# source_A.net
KiCad netlist of a schematic drawn in Altium Designer
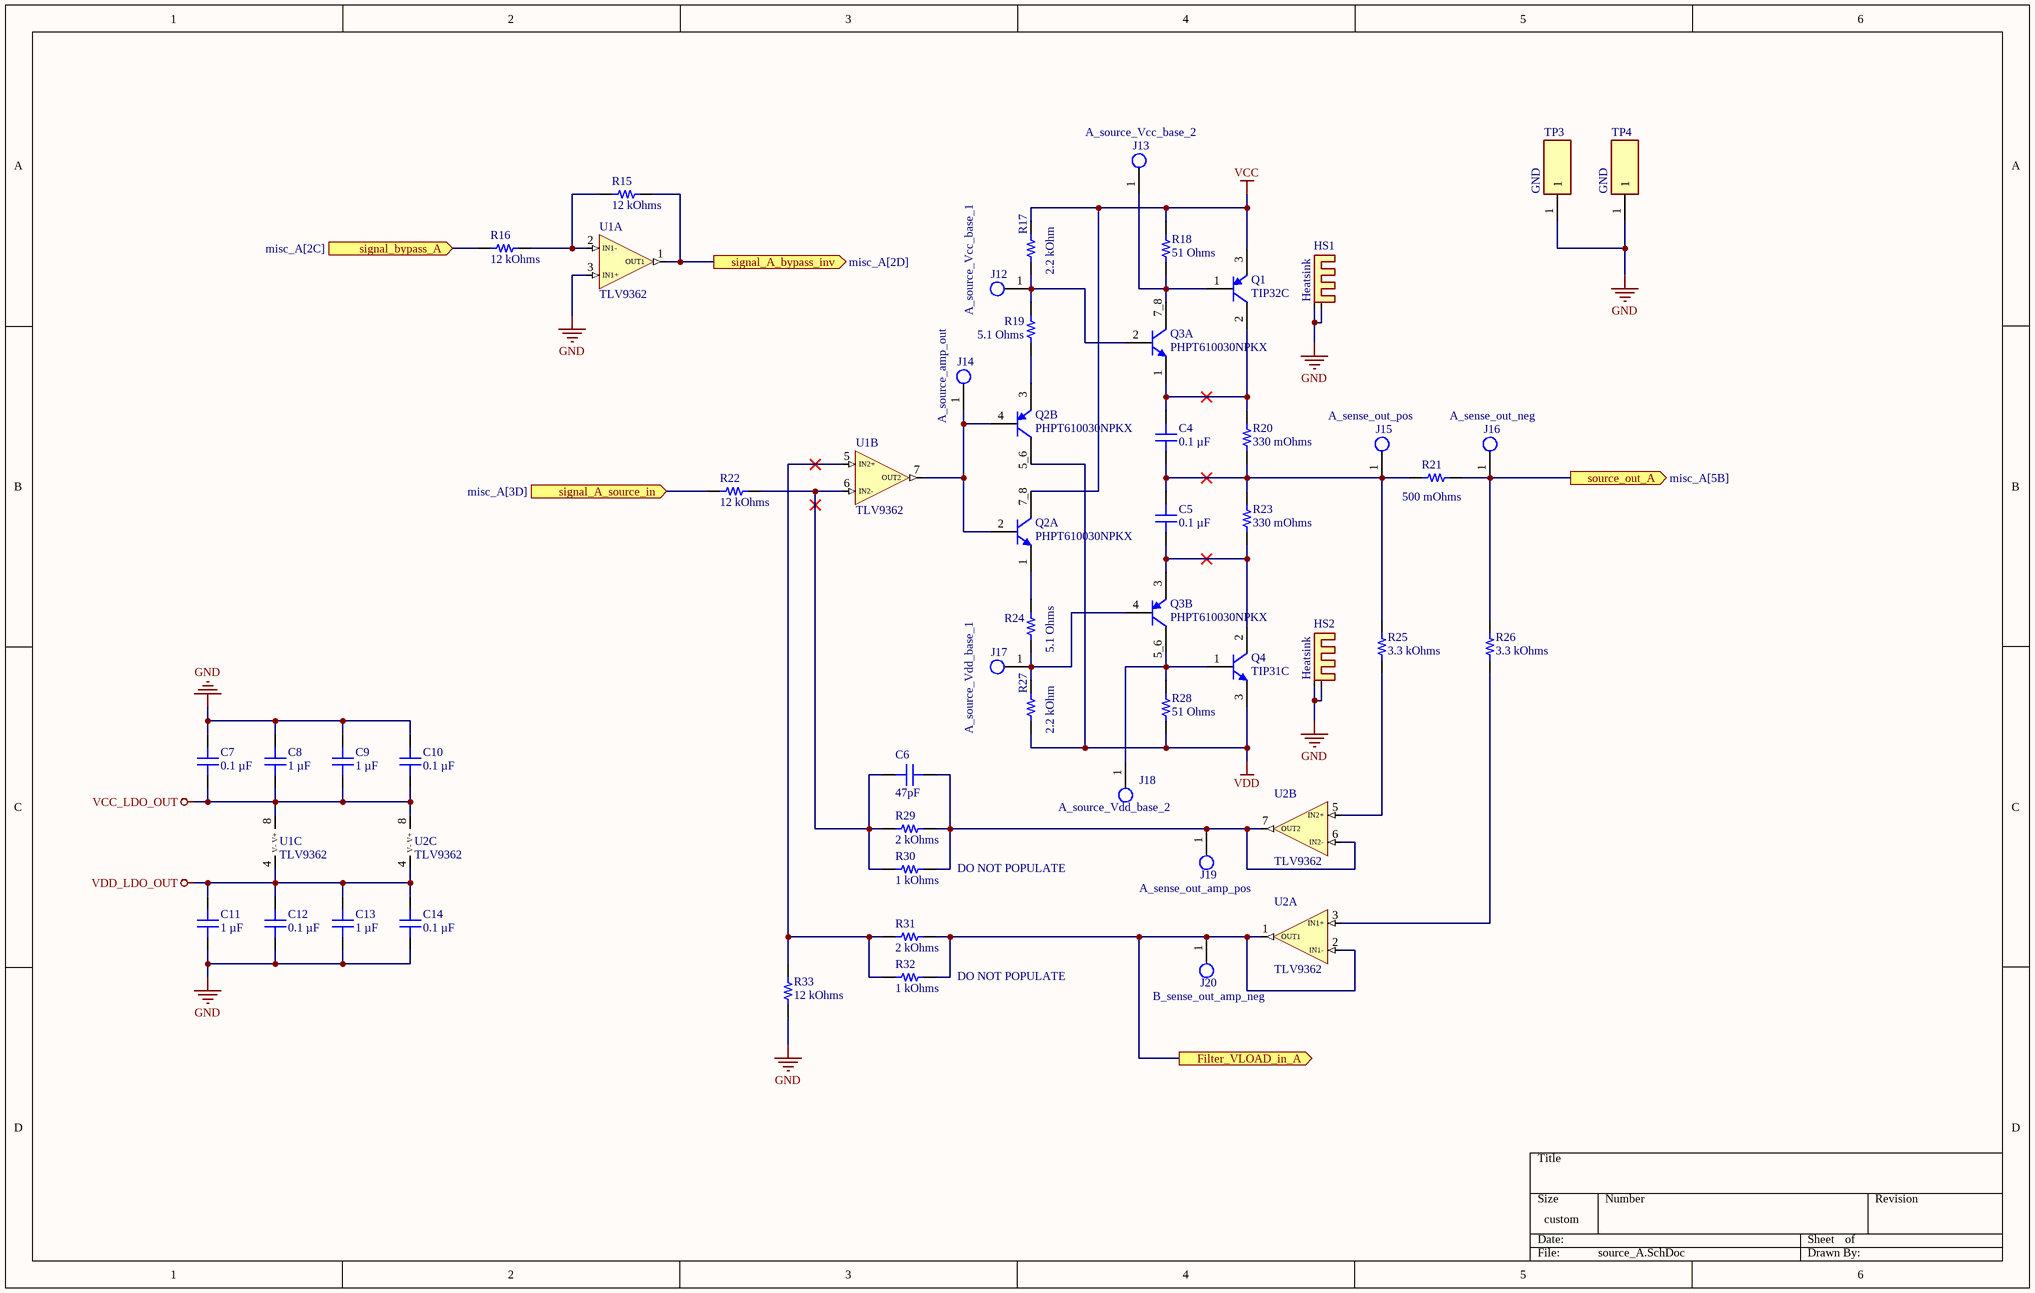
[diagram p0: source_A.SchDoc]

(export (version "E")
  (design (tool "Eeschema 10.0.6"))
  (components
    (comp (ref "C4")
      (value "0.1 µF")
      (footprint "CAP 1206_3216 - 0.8MM")
      (description "CAP CER 0.1UF 50V X7R 1206")
      (fields
        (field (name "PART NUMBER") "885012208087")
        (field (name "CAPACITANCE") "0.1 µF")
        (field (name "MANUFACTURER") "Würth Elektronik")
      )
      (libsource (lib "Celestial Altium Library - altium_library") (part "Capacitor"))
    )
    (comp (ref "C5")
      (value "0.1 µF")
      (footprint "CAP 1206_3216 - 0.8MM")
      (description "CAP CER 0.1UF 50V X7R 1206")
      (fields
        (field (name "PART NUMBER") "885012208087")
        (field (name "CAPACITANCE") "0.1 µF")
        (field (name "MANUFACTURER") "Würth Elektronik")
      )
      (libsource (lib "Celestial Altium Library - altium_library") (part "Capacitor"))
    )
    (comp (ref "C6")
      (value "47pF")
      (footprint "CAP 1206_3216 - 1.8MM")
      (description "CAP CER 47PF 1KV C0G/NP0 1206")
      (fields
        (field (name "PART NUMBER") "1206AA470KAT1A")
        (field (name "CAPACITANCE") "47pF")
        (field (name "MANUFACTURER") "AVX Corporation")
      )
      (libsource (lib "Celestial Altium Library - altium_library") (part "Capacitor"))
    )
    (comp (ref "C7")
      (value "0.1 µF")
      (footprint "CAP 1206_3216 - 0.8MM")
      (description "CAP CER 0.1UF 50V X7R 1206")
      (fields
        (field (name "PART NUMBER") "885012208087")
        (field (name "CAPACITANCE") "0.1 µF")
        (field (name "MANUFACTURER") "Würth Elektronik")
      )
      (libsource (lib "Celestial Altium Library - altium_library") (part "Capacitor"))
    )
    (comp (ref "C8")
      (value "1 µF")
      (footprint "CAP 1206_3216 - 0.8MM")
      (description "CAP CER 1UF 50V X7R 1206")
      (fields
        (field (name "PART NUMBER") "885012208093")
        (field (name "CAPACITANCE") "1 µF")
        (field (name "MANUFACTURER") "Würth Elektronik")
      )
      (libsource (lib "Celestial Altium Library - altium_library") (part "Capacitor"))
    )
    (comp (ref "C9")
      (value "1 µF")
      (footprint "CAP 1206_3216 - 0.8MM")
      (description "CAP CER 1UF 50V X7R 1206")
      (fields
        (field (name "PART NUMBER") "885012208093")
        (field (name "CAPACITANCE") "1 µF")
        (field (name "MANUFACTURER") "Würth Elektronik")
      )
      (libsource (lib "Celestial Altium Library - altium_library") (part "Capacitor"))
    )
    (comp (ref "C10")
      (value "0.1 µF")
      (footprint "CAP 1206_3216 - 0.8MM")
      (description "CAP CER 0.1UF 50V X7R 1206")
      (fields
        (field (name "PART NUMBER") "885012208087")
        (field (name "CAPACITANCE") "0.1 µF")
        (field (name "MANUFACTURER") "Würth Elektronik")
      )
      (libsource (lib "Celestial Altium Library - altium_library") (part "Capacitor"))
    )
    (comp (ref "C11")
      (value "1 µF")
      (footprint "CAP 1206_3216 - 0.8MM")
      (description "CAP CER 1UF 50V X7R 1206")
      (fields
        (field (name "PART NUMBER") "885012208093")
        (field (name "CAPACITANCE") "1 µF")
        (field (name "MANUFACTURER") "Würth Elektronik")
      )
      (libsource (lib "Celestial Altium Library - altium_library") (part "Capacitor"))
    )
    (comp (ref "C12")
      (value "0.1 µF")
      (footprint "CAP 1206_3216 - 0.8MM")
      (description "CAP CER 0.1UF 50V X7R 1206")
      (fields
        (field (name "PART NUMBER") "885012208087")
        (field (name "CAPACITANCE") "0.1 µF")
        (field (name "MANUFACTURER") "Würth Elektronik")
      )
      (libsource (lib "Celestial Altium Library - altium_library") (part "Capacitor"))
    )
    (comp (ref "C13")
      (value "1 µF")
      (footprint "CAP 1206_3216 - 0.8MM")
      (description "CAP CER 1UF 50V X7R 1206")
      (fields
        (field (name "PART NUMBER") "885012208093")
        (field (name "CAPACITANCE") "1 µF")
        (field (name "MANUFACTURER") "Würth Elektronik")
      )
      (libsource (lib "Celestial Altium Library - altium_library") (part "Capacitor"))
    )
    (comp (ref "C14")
      (value "0.1 µF")
      (footprint "CAP 1206_3216 - 0.8MM")
      (description "CAP CER 0.1UF 50V X7R 1206")
      (fields
        (field (name "PART NUMBER") "885012208087")
        (field (name "CAPACITANCE") "0.1 µF")
        (field (name "MANUFACTURER") "Würth Elektronik")
      )
      (libsource (lib "Celestial Altium Library - altium_library") (part "Capacitor"))
    )
    (comp (ref "HS1")
      (value "Heatsink")
      (footprint "593002B03400G")
      (description "593002B03400G Heatsink TO220 13.4 C/W")
      (fields
        (field (name "MANUFACTURER_PART_NUMBER") "593002B03400G")
        (field (name "MOUSER PART NUMBER") "532-593002B03400G")
      )
      (libsource (lib "za_koncar") (part "593002B03400G"))
    )
    (comp (ref "HS2")
      (value "Heatsink")
      (footprint "593002B03400G")
      (description "593002B03400G Heatsink TO220 13.4 C/W")
      (fields
        (field (name "MANUFACTURER_PART_NUMBER") "593002B03400G")
        (field (name "MOUSER PART NUMBER") "532-593002B03400G")
      )
      (libsource (lib "za_koncar") (part "593002B03400G"))
    )
    (comp (ref "J12")
      (value "A_source_Vcc_base_1")
      (footprint "FP-5001-MFG")
      (description "PC TEST POINT MINIATURE BLACK")
      (libsource (lib "za_koncar") (part "5001"))
    )
    (comp (ref "J13")
      (value "A_source_Vcc_base_2")
      (footprint "FP-5001-MFG")
      (description "PC TEST POINT MINIATURE BLACK")
      (libsource (lib "za_koncar") (part "5001"))
    )
    (comp (ref "J14")
      (value "A_source_amp_out")
      (footprint "FP-5001-MFG")
      (description "PC TEST POINT MINIATURE BLACK")
      (libsource (lib "za_koncar") (part "5001"))
    )
    (comp (ref "J15")
      (value "A_sense_out_pos")
      (footprint "FP-5001-MFG")
      (description "PC TEST POINT MINIATURE BLACK")
      (libsource (lib "za_koncar") (part "5001"))
    )
    (comp (ref "J16")
      (value "A_sense_out_neg")
      (footprint "FP-5001-MFG")
      (description "PC TEST POINT MINIATURE BLACK")
      (libsource (lib "za_koncar") (part "5001"))
    )
    (comp (ref "J17")
      (value "A_source_Vdd_base_1")
      (footprint "FP-5001-MFG")
      (description "PC TEST POINT MINIATURE BLACK")
      (libsource (lib "za_koncar") (part "5001"))
    )
    (comp (ref "J18")
      (value "A_source_Vdd_base_2")
      (footprint "FP-5001-MFG")
      (description "PC TEST POINT MINIATURE BLACK")
      (libsource (lib "za_koncar") (part "5001"))
    )
    (comp (ref "J19")
      (value "A_sense_out_amp_pos")
      (footprint "FP-5001-MFG")
      (description "PC TEST POINT MINIATURE BLACK")
      (libsource (lib "za_koncar") (part "5001"))
    )
    (comp (ref "J20")
      (value "B_sense_out_amp_neg")
      (footprint "FP-5001-MFG")
      (description "PC TEST POINT MINIATURE BLACK")
      (libsource (lib "za_koncar") (part "5001"))
    )
    (comp (ref "Q1")
      (value "TIP32C")
      (footprint "ONSC-TO-220-3-221A-09")
      (description "Complementary Silicon Plastic Power Transistor, 3-Pin TO-220, Tube")
      (fields (field (name "MANUFACTURER") "On Semiconductor"))
      (libsource (lib "ON Semi General Purpose Transistors") (part "TIP32C"))
    )
    (comp (ref "Q2")
      (value "PHPT610030NPKX")
      (footprint "TRANS_BUK9K18-40E,115")
      (libsource (lib "za_koncar") (part "PHPT610030NPK"))
    )
    (comp (ref "Q3")
      (value "PHPT610030NPKX")
      (footprint "TRANS_BUK9K18-40E,115")
      (libsource (lib "za_koncar") (part "PHPT610030NPK"))
    )
    (comp (ref "Q4")
      (value "TIP31C")
      (footprint "ONSC-TO-220-3-221A-09")
      (description "Complementary Silicon Plastic Power Transistor, 3-Pin TO-220, Tube")
      (fields (field (name "MANUFACTURER") "On Semiconductor"))
      (libsource (lib "ON Semi General Purpose Transistors") (part "TIP31C"))
    )
    (comp (ref "R15")
      (value "12 kOhms")
      (footprint "RES 1206_3216")
      (description "RES SMD 12K OHM 0.1% 1/4W 1206")
      (fields
        (field (name "PART NUMBER") "ERA-8AEB123V")
        (field (name "MANUFACTURER") "Panasonic Electronic Components")
      )
      (libsource (lib "Celestial Altium Library - altium_library") (part "Resistor"))
    )
    (comp (ref "R16")
      (value "12 kOhms")
      (footprint "RES 1206_3216")
      (description "RES SMD 12K OHM 0.1% 1/4W 1206")
      (fields
        (field (name "PART NUMBER") "ERA-8AEB123V")
        (field (name "MANUFACTURER") "Panasonic Electronic Components")
      )
      (libsource (lib "Celestial Altium Library - altium_library") (part "Resistor"))
    )
    (comp (ref "R17")
      (value "2.2 kOhm")
      (footprint "za_koncar:RESC3116X65N")
      (description "Resistor")
      (fields
        (field (name "MANUFACTURER_PART_NUMBER") "RT1206FRE072K2L")
        (field (name "MOUSER PART NUMBER") "603-RT1206FRE072K2L")
      )
      (libsource (lib "za_koncar") (part "RT1206FRE072K2L"))
    )
    (comp (ref "R18")
      (value "51 Ohms")
      (footprint "RES 1206_3216")
      (description "RES SMD 51 OHM 5% 1/4W 1206")
      (fields
        (field (name "PART NUMBER") "ERJ-8GEYJ510V")
        (field (name "MANUFACTURER") "Panasonic Electronic Components")
      )
      (libsource (lib "Celestial Altium Library - altium_library") (part "Resistor"))
    )
    (comp (ref "R19")
      (value "5.1 Ohms")
      (footprint "RES 1206_3216")
      (description "RES SMD 5.1 OHM 5% 1/4W 1206")
      (fields
        (field (name "PART NUMBER") "ERJ-8GEYJ5R1V")
        (field (name "MANUFACTURER") "Panasonic Electronic Components")
      )
      (libsource (lib "Celestial Altium Library - altium_library") (part "Resistor"))
    )
    (comp (ref "R20")
      (value "330 mOhms")
      (footprint "STACKPOLE CSR2512")
      (description "RES 0.33 OHM 1% 2W 2512")
      (fields
        (field (name "PART NUMBER") "CSRN2512FKR330")
        (field (name "MANUFACTURER") "Stackpole Electronics Inc")
      )
      (libsource (lib "Celestial Altium Library - altium_library") (part "Resistor"))
    )
    (comp (ref "R21")
      (value "500 mOhms")
      (footprint "STACKPOLE CSR2512")
      (description "RES 0.5 OHM 1% 2W 2512")
      (fields
        (field (name "PART NUMBER") "CSRN2512FKR500")
        (field (name "MANUFACTURER") "Stackpole Electronics Inc")
      )
      (libsource (lib "Celestial Altium Library - altium_library") (part "Resistor"))
    )
    (comp (ref "R22")
      (value "12 kOhms")
      (footprint "RES 1206_3216")
      (description "RES SMD 12K OHM 0.1% 1/4W 1206")
      (fields
        (field (name "PART NUMBER") "ERA-8AEB123V")
        (field (name "MANUFACTURER") "Panasonic Electronic Components")
      )
      (libsource (lib "Celestial Altium Library - altium_library") (part "Resistor"))
    )
    (comp (ref "R23")
      (value "330 mOhms")
      (footprint "STACKPOLE CSR2512")
      (description "RES 0.33 OHM 1% 2W 2512")
      (fields
        (field (name "PART NUMBER") "CSRN2512FKR330")
        (field (name "MANUFACTURER") "Stackpole Electronics Inc")
      )
      (libsource (lib "Celestial Altium Library - altium_library") (part "Resistor"))
    )
    (comp (ref "R24")
      (value "5.1 Ohms")
      (footprint "RES 1206_3216")
      (description "RES SMD 5.1 OHM 5% 1/4W 1206")
      (fields
        (field (name "PART NUMBER") "ERJ-8GEYJ5R1V")
        (field (name "MANUFACTURER") "Panasonic Electronic Components")
      )
      (libsource (lib "Celestial Altium Library - altium_library") (part "Resistor"))
    )
    (comp (ref "R25")
      (value "3.3 kOhms")
      (footprint "YAGEO RES 1206_3216")
      (description "RES SMD 3.3K OHM 1% 1/4W 1206")
      (fields (field (name "PART NUMBER") "RT1206FRE073K3L") (field (name "MANUFACTURER") "Yageo"))
      (libsource (lib "Celestial Altium Library - altium_library") (part "Resistor"))
    )
    (comp (ref "R26")
      (value "3.3 kOhms")
      (footprint "YAGEO RES 1206_3216")
      (description "RES SMD 3.3K OHM 1% 1/4W 1206")
      (fields (field (name "PART NUMBER") "RT1206FRE073K3L") (field (name "MANUFACTURER") "Yageo"))
      (libsource (lib "Celestial Altium Library - altium_library") (part "Resistor"))
    )
    (comp (ref "R27")
      (value "2.2 kOhm")
      (footprint "za_koncar:RESC3116X65N")
      (description "Resistor")
      (fields
        (field (name "MANUFACTURER_PART_NUMBER") "RT1206FRE072K2L")
        (field (name "MOUSER PART NUMBER") "603-RT1206FRE072K2L")
      )
      (libsource (lib "za_koncar") (part "RT1206FRE072K2L"))
    )
    (comp (ref "R28")
      (value "51 Ohms")
      (footprint "RES 1206_3216")
      (description "RES SMD 51 OHM 5% 1/4W 1206")
      (fields
        (field (name "PART NUMBER") "ERJ-8GEYJ510V")
        (field (name "MANUFACTURER") "Panasonic Electronic Components")
      )
      (libsource (lib "Celestial Altium Library - altium_library") (part "Resistor"))
    )
    (comp (ref "R29")
      (value "2 kOhms")
      (footprint "RES 1206_3216")
      (description "RES SMD 2K OHM 0.1% 1/4W 1206")
      (fields
        (field (name "PART NUMBER") "ERA-8AEB202V")
        (field (name "MANUFACTURER") "Panasonic Electronic Components")
      )
      (libsource (lib "Celestial Altium Library - altium_library") (part "Resistor"))
    )
    (comp (ref "R30")
      (value "1 kOhms")
      (footprint "RES 1206_3216")
      (description "RES SMD 1K OHM 0.1% 1/4W 1206")
      (fields
        (field (name "PART NUMBER") "ERA-8AEB102V")
        (field (name "MANUFACTURER") "Panasonic Electronic Components")
      )
      (libsource (lib "Celestial Altium Library - altium_library") (part "Resistor"))
    )
    (comp (ref "R31")
      (value "2 kOhms")
      (footprint "RES 1206_3216")
      (description "RES SMD 2K OHM 0.1% 1/4W 1206")
      (fields
        (field (name "PART NUMBER") "ERA-8AEB202V")
        (field (name "MANUFACTURER") "Panasonic Electronic Components")
      )
      (libsource (lib "Celestial Altium Library - altium_library") (part "Resistor"))
    )
    (comp (ref "R32")
      (value "1 kOhms")
      (footprint "RES 1206_3216")
      (description "RES SMD 1K OHM 0.1% 1/4W 1206")
      (fields
        (field (name "PART NUMBER") "ERA-8AEB102V")
        (field (name "MANUFACTURER") "Panasonic Electronic Components")
      )
      (libsource (lib "Celestial Altium Library - altium_library") (part "Resistor"))
    )
    (comp (ref "R33")
      (value "12 kOhms")
      (footprint "RES 1206_3216")
      (description "RES SMD 12K OHM 0.1% 1/4W 1206")
      (fields
        (field (name "PART NUMBER") "ERA-8AEB123V")
        (field (name "MANUFACTURER") "Panasonic Electronic Components")
      )
      (libsource (lib "Celestial Altium Library - altium_library") (part "Resistor"))
    )
    (comp (ref "TP3")
      (value "GND")
      (footprint "za_koncar:S175146R")
      (description "Test Point")
      (fields
        (field (name "MANUFACTURER_PART_NUMBER") "S1751-46R")
        (field (name "MOUSER PART NUMBER") "855-S1751-46R")
      )
      (libsource (lib "za_koncar") (part "S1751-46R"))
    )
    (comp (ref "TP4")
      (value "GND")
      (footprint "za_koncar:S175146R")
      (description "Test Point")
      (fields
        (field (name "MANUFACTURER_PART_NUMBER") "S1751-46R")
        (field (name "MOUSER PART NUMBER") "855-S1751-46R")
      )
      (libsource (lib "za_koncar") (part "S1751-46R"))
    )
    (comp (ref "U1")
      (value "TLV9362")
      (footprint "SOIC8-127P600X175-8N")
      (description "TLV936x 10-MHz, 40-V, RRO, Operational Amplifie")
      (libsource (lib "za_koncar") (part "TLV9362"))
    )
    (comp (ref "U2")
      (value "TLV9362")
      (footprint "SOIC8-127P600X175-8N")
      (description "TLV936x 10-MHz, 40-V, RRO, Operational Amplifie")
      (libsource (lib "za_koncar") (part "TLV9362"))
    )
  )
  (nets
    (net (code "1") (name "/Filter_VLOAD_in_A") (class "Default")
      (node (ref "J20") (pin "1") (pinfunction "1_1") (pintype "passive"))
      (node (ref "R31") (pin "2") (pinfunction "2_2") (pintype "passive"))
      (node (ref "R32") (pin "2") (pinfunction "2_2") (pintype "passive"))
      (node (ref "U2") (pin "1") (pinfunction "OUT1_1") (pintype "output"))
      (node (ref "U2") (pin "2") (pinfunction "IN1-_2") (pintype "input"))
    )
    (net (code "2") (name "/signal_A_bypass_inv") (class "Default")
      (node (ref "R15") (pin "2") (pinfunction "2_2") (pintype "passive"))
      (node (ref "U1") (pin "1") (pinfunction "OUT1_1") (pintype "output"))
    )
    (net (code "3") (name "/signal_A_source_in") (class "Default")
      (node (ref "R22") (pin "2") (pinfunction "2_2") (pintype "passive"))
    )
    (net (code "4") (name "/signal_bypass_A") (class "Default")
      (node (ref "R16") (pin "2") (pinfunction "2_2") (pintype "passive"))
    )
    (net (code "5") (name "/source_out_A") (class "Default")
      (node (ref "J16") (pin "1") (pinfunction "1_1") (pintype "passive"))
      (node (ref "R21") (pin "1") (pinfunction "1_1") (pintype "passive"))
      (node (ref "R26") (pin "1") (pinfunction "1_1") (pintype "passive"))
    )
    (net (code "6") (name "GND") (class "Default")
      (node (ref "C10") (pin "2") (pinfunction "2_2") (pintype "passive"))
      (node (ref "C11") (pin "2") (pinfunction "2_2") (pintype "passive"))
      (node (ref "C12") (pin "2") (pinfunction "2_2") (pintype "passive"))
      (node (ref "C13") (pin "2") (pinfunction "2_2") (pintype "passive"))
      (node (ref "C14") (pin "2") (pinfunction "2_2") (pintype "passive"))
      (node (ref "C7") (pin "1") (pinfunction "1_1") (pintype "passive"))
      (node (ref "C8") (pin "1") (pinfunction "1_1") (pintype "passive"))
      (node (ref "C9") (pin "2") (pinfunction "2_2") (pintype "passive"))
      (node (ref "HS1") (pin "1") (pinfunction "1_1") (pintype "passive"))
      (node (ref "HS1") (pin "2") (pinfunction "2_2") (pintype "passive"))
      (node (ref "HS2") (pin "1") (pinfunction "1_1") (pintype "passive"))
      (node (ref "HS2") (pin "2") (pinfunction "2_2") (pintype "passive"))
      (node (ref "R33") (pin "1") (pinfunction "1_1") (pintype "passive"))
      (node (ref "TP3") (pin "1") (pinfunction "1_1") (pintype "passive"))
      (node (ref "TP4") (pin "1") (pinfunction "1_1") (pintype "passive"))
      (node (ref "U1") (pin "3") (pinfunction "IN1+_3") (pintype "input"))
    )
    (net (code "7") (name "Net-(C4-Pad1)") (class "Default")
      (node (ref "C4") (pin "1") (pinfunction "1_1") (pintype "passive"))
      (node (ref "C5") (pin "2") (pinfunction "2_2") (pintype "passive"))
      (node (ref "J15") (pin "1") (pinfunction "1_1") (pintype "passive"))
      (node (ref "R20") (pin "1") (pinfunction "1_1") (pintype "passive"))
      (node (ref "R21") (pin "2") (pinfunction "2_2") (pintype "passive"))
      (node (ref "R23") (pin "2") (pinfunction "2_2") (pintype "passive"))
      (node (ref "R25") (pin "1") (pinfunction "1_1") (pintype "passive"))
    )
    (net (code "8") (name "Net-(Q1-B)") (class "Default")
      (node (ref "J13") (pin "1") (pinfunction "1_1") (pintype "passive"))
      (node (ref "Q1") (pin "1") (pinfunction "B_1") (pintype "passive"))
      (node (ref "Q3") (pin "7_8") (pinfunction "C1_7_8") (pintype "passive"))
      (node (ref "R18") (pin "1") (pinfunction "1_1") (pintype "passive"))
    )
    (net (code "9") (name "Net-(Q1-C)") (class "Default")
      (node (ref "C4") (pin "2") (pinfunction "2_2") (pintype "passive"))
      (node (ref "Q1") (pin "2") (pinfunction "C_2") (pintype "passive"))
      (node (ref "Q3") (pin "1") (pinfunction "E1_1") (pintype "passive"))
      (node (ref "R20") (pin "2") (pinfunction "2_2") (pintype "passive"))
    )
    (net (code "10") (name "Net-(Q2A-B1)") (class "Default")
      (node (ref "J14") (pin "1") (pinfunction "1_1") (pintype "passive"))
      (node (ref "Q2") (pin "2") (pinfunction "B1_2") (pintype "passive"))
      (node (ref "Q2") (pin "4") (pinfunction "B2_4") (pintype "passive"))
      (node (ref "U1") (pin "7") (pinfunction "OUT2_7") (pintype "output"))
    )
    (net (code "11") (name "Net-(Q2A-E1)") (class "Default")
      (node (ref "Q2") (pin "1") (pinfunction "E1_1") (pintype "passive"))
      (node (ref "R24") (pin "2") (pinfunction "2_2") (pintype "passive"))
    )
    (net (code "12") (name "Net-(Q2B-E2)") (class "Default")
      (node (ref "Q2") (pin "3") (pinfunction "E2_3") (pintype "passive"))
      (node (ref "R19") (pin "1") (pinfunction "1_1") (pintype "passive"))
    )
    (net (code "13") (name "Net-(Q3A-B1)") (class "Default")
      (node (ref "J12") (pin "1") (pinfunction "1_1") (pintype "passive"))
      (node (ref "Q3") (pin "2") (pinfunction "B1_2") (pintype "passive"))
      (node (ref "R17") (pin "1") (pinfunction "1_1") (pintype "passive"))
      (node (ref "R19") (pin "2") (pinfunction "2_2") (pintype "passive"))
    )
    (net (code "14") (name "Net-(Q3B-B2)") (class "Default")
      (node (ref "J17") (pin "1") (pinfunction "1_1") (pintype "passive"))
      (node (ref "Q3") (pin "4") (pinfunction "B2_4") (pintype "passive"))
      (node (ref "R24") (pin "1") (pinfunction "1_1") (pintype "passive"))
      (node (ref "R27") (pin "2") (pinfunction "2_2") (pintype "passive"))
    )
    (net (code "15") (name "Net-(Q3B-C2)") (class "Default")
      (node (ref "J18") (pin "1") (pinfunction "1_1") (pintype "passive"))
      (node (ref "Q3") (pin "5_6") (pinfunction "C2_5_6") (pintype "passive"))
      (node (ref "Q4") (pin "1") (pinfunction "B_1") (pintype "passive"))
      (node (ref "R28") (pin "2") (pinfunction "2_2") (pintype "passive"))
    )
    (net (code "16") (name "Net-(Q3B-E2)") (class "Default")
      (node (ref "C5") (pin "1") (pinfunction "1_1") (pintype "passive"))
      (node (ref "Q3") (pin "3") (pinfunction "E2_3") (pintype "passive"))
      (node (ref "Q4") (pin "2") (pinfunction "C_2") (pintype "passive"))
      (node (ref "R23") (pin "1") (pinfunction "1_1") (pintype "passive"))
    )
    (net (code "17") (name "Net-(U1A-IN1-)") (class "Default")
      (node (ref "R15") (pin "1") (pinfunction "1_1") (pintype "passive"))
      (node (ref "R16") (pin "1") (pinfunction "1_1") (pintype "passive"))
      (node (ref "U1") (pin "2") (pinfunction "IN1-_2") (pintype "input"))
    )
    (net (code "18") (name "Net-(U1B-IN2+)") (class "Default")
      (node (ref "R31") (pin "1") (pinfunction "1_1") (pintype "passive"))
      (node (ref "R32") (pin "1") (pinfunction "1_1") (pintype "passive"))
      (node (ref "R33") (pin "2") (pinfunction "2_2") (pintype "passive"))
      (node (ref "U1") (pin "5") (pinfunction "IN2+_5") (pintype "input"))
    )
    (net (code "19") (name "Net-(U1B-IN2-)") (class "Default")
      (node (ref "C6") (pin "1") (pinfunction "1_1") (pintype "passive"))
      (node (ref "R22") (pin "1") (pinfunction "1_1") (pintype "passive"))
      (node (ref "R29") (pin "1") (pinfunction "1_1") (pintype "passive"))
      (node (ref "R30") (pin "1") (pinfunction "1_1") (pintype "passive"))
      (node (ref "U1") (pin "6") (pinfunction "IN2-_6") (pintype "input"))
    )
    (net (code "20") (name "Net-(U2A-IN1+)") (class "Default")
      (node (ref "R26") (pin "2") (pinfunction "2_2") (pintype "passive"))
      (node (ref "U2") (pin "3") (pinfunction "IN1+_3") (pintype "input"))
    )
    (net (code "21") (name "Net-(U2B-IN2+)") (class "Default")
      (node (ref "R25") (pin "2") (pinfunction "2_2") (pintype "passive"))
      (node (ref "U2") (pin "5") (pinfunction "IN2+_5") (pintype "input"))
    )
    (net (code "22") (name "Net-(U2B-IN2-)") (class "Default")
      (node (ref "C6") (pin "2") (pinfunction "2_2") (pintype "passive"))
      (node (ref "J19") (pin "1") (pinfunction "1_1") (pintype "passive"))
      (node (ref "R29") (pin "2") (pinfunction "2_2") (pintype "passive"))
      (node (ref "R30") (pin "2") (pinfunction "2_2") (pintype "passive"))
      (node (ref "U2") (pin "6") (pinfunction "IN2-_6") (pintype "input"))
      (node (ref "U2") (pin "7") (pinfunction "OUT2_7") (pintype "output"))
    )
    (net (code "23") (name "VCC") (class "Default")
      (node (ref "Q1") (pin "3") (pinfunction "E_3") (pintype "passive"))
      (node (ref "Q2") (pin "7_8") (pinfunction "C1_7_8") (pintype "passive"))
      (node (ref "R17") (pin "2") (pinfunction "2_2") (pintype "passive"))
      (node (ref "R18") (pin "2") (pinfunction "2_2") (pintype "passive"))
    )
    (net (code "24") (name "VCC_LDO_OUT") (class "Default")
      (node (ref "C10") (pin "1") (pinfunction "1_1") (pintype "passive"))
      (node (ref "C7") (pin "2") (pinfunction "2_2") (pintype "passive"))
      (node (ref "C8") (pin "2") (pinfunction "2_2") (pintype "passive"))
      (node (ref "C9") (pin "1") (pinfunction "1_1") (pintype "passive"))
      (node (ref "U1") (pin "8") (pinfunction "V+_8") (pintype "power_in"))
      (node (ref "U2") (pin "8") (pinfunction "V+_8") (pintype "power_in"))
    )
    (net (code "25") (name "VDD") (class "Default")
      (node (ref "Q2") (pin "5_6") (pinfunction "C2_5_6") (pintype "passive"))
      (node (ref "Q4") (pin "3") (pinfunction "E_3") (pintype "passive"))
      (node (ref "R27") (pin "1") (pinfunction "1_1") (pintype "passive"))
      (node (ref "R28") (pin "1") (pinfunction "1_1") (pintype "passive"))
    )
    (net (code "26") (name "VDD_LDO_OUT") (class "Default")
      (node (ref "C11") (pin "1") (pinfunction "1_1") (pintype "passive"))
      (node (ref "C12") (pin "1") (pinfunction "1_1") (pintype "passive"))
      (node (ref "C13") (pin "1") (pinfunction "1_1") (pintype "passive"))
      (node (ref "C14") (pin "1") (pinfunction "1_1") (pintype "passive"))
      (node (ref "U1") (pin "4") (pinfunction "V-_4") (pintype "power_in"))
      (node (ref "U2") (pin "4") (pinfunction "V-_4") (pintype "power_in"))
    )
  )
)
